# Motor_Drivers.net
KiCad netlist of a schematic drawn in Altium Designer
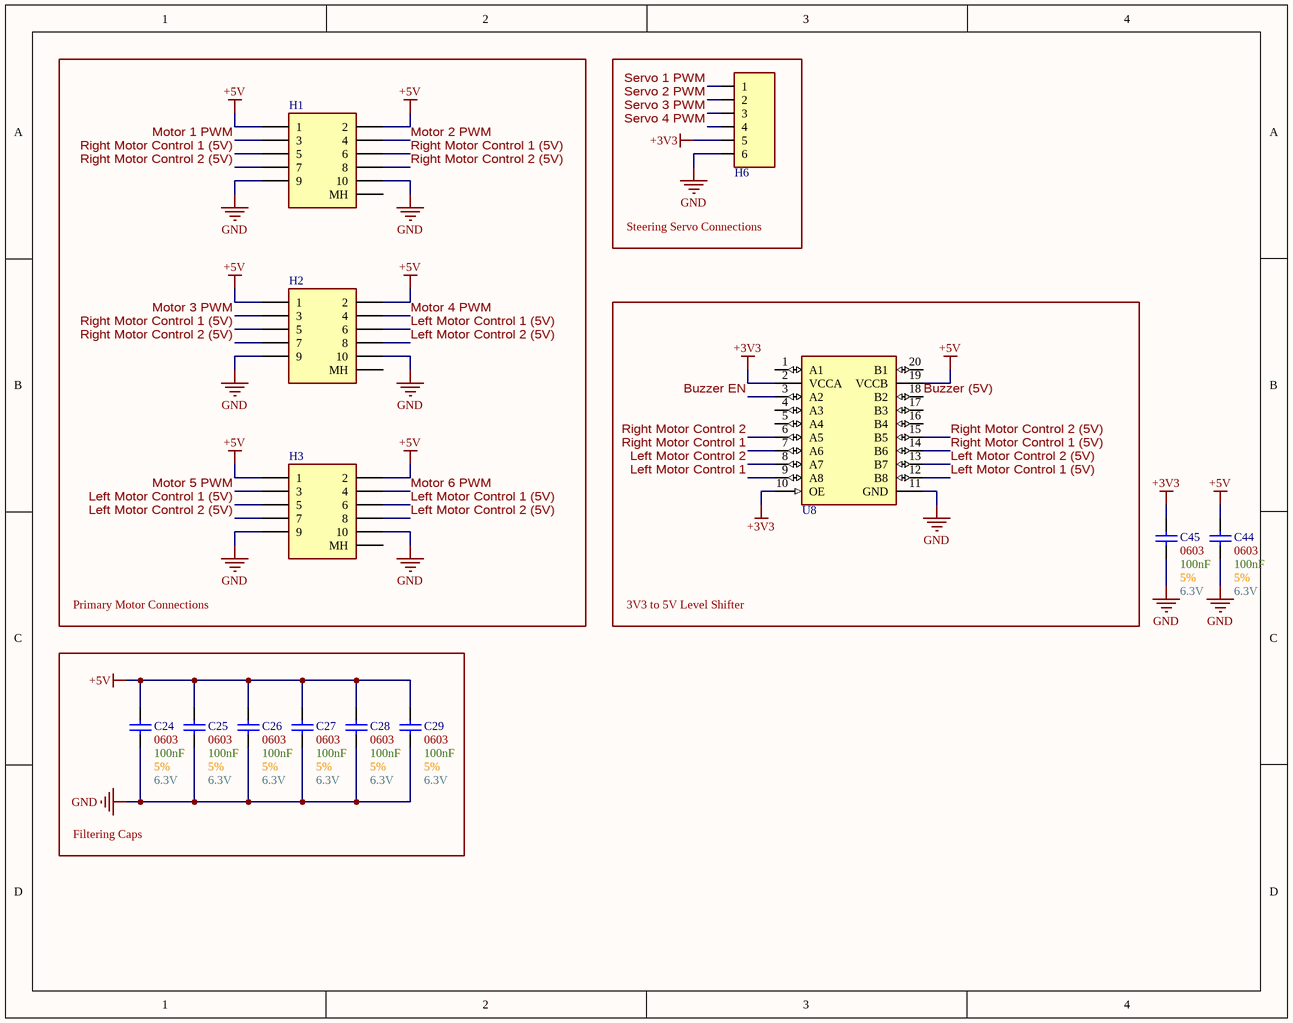
[diagram p0: Motor Drivers.SchDoc]

(export (version "E")
  (design (tool "Eeschema 10.0.6"))
  (components
    (comp (ref "C24")
      (value "[Cap] SMD Nonpolarized")
      (footprint "[Cap] SMD 0603")
      (fields
        (field (name "SIZE PACKAGE") "0603")
        (field (name "CAPACITANCE") "100nF")
        (field (name "VOLTAGE") "6.3V")
        (field (name "TOLERANCE") "5%")
      )
      (libsource (lib "RADM Components") (part "[Cap] SMD Nonpolarized"))
    )
    (comp (ref "C25")
      (value "[Cap] SMD Nonpolarized")
      (footprint "[Cap] SMD 0603")
      (fields
        (field (name "SIZE PACKAGE") "0603")
        (field (name "CAPACITANCE") "100nF")
        (field (name "VOLTAGE") "6.3V")
        (field (name "TOLERANCE") "5%")
      )
      (libsource (lib "RADM Components") (part "[Cap] SMD Nonpolarized"))
    )
    (comp (ref "C26")
      (value "[Cap] SMD Nonpolarized")
      (footprint "[Cap] SMD 0603")
      (fields
        (field (name "SIZE PACKAGE") "0603")
        (field (name "CAPACITANCE") "100nF")
        (field (name "VOLTAGE") "6.3V")
        (field (name "TOLERANCE") "5%")
      )
      (libsource (lib "RADM Components") (part "[Cap] SMD Nonpolarized"))
    )
    (comp (ref "C27")
      (value "[Cap] SMD Nonpolarized")
      (footprint "[Cap] SMD 0603")
      (fields
        (field (name "SIZE PACKAGE") "0603")
        (field (name "CAPACITANCE") "100nF")
        (field (name "VOLTAGE") "6.3V")
        (field (name "TOLERANCE") "5%")
      )
      (libsource (lib "RADM Components") (part "[Cap] SMD Nonpolarized"))
    )
    (comp (ref "C28")
      (value "[Cap] SMD Nonpolarized")
      (footprint "[Cap] SMD 0603")
      (fields
        (field (name "SIZE PACKAGE") "0603")
        (field (name "CAPACITANCE") "100nF")
        (field (name "VOLTAGE") "6.3V")
        (field (name "TOLERANCE") "5%")
      )
      (libsource (lib "RADM Components") (part "[Cap] SMD Nonpolarized"))
    )
    (comp (ref "C29")
      (value "[Cap] SMD Nonpolarized")
      (footprint "[Cap] SMD 0603")
      (fields
        (field (name "SIZE PACKAGE") "0603")
        (field (name "CAPACITANCE") "100nF")
        (field (name "VOLTAGE") "6.3V")
        (field (name "TOLERANCE") "5%")
      )
      (libsource (lib "RADM Components") (part "[Cap] SMD Nonpolarized"))
    )
    (comp (ref "C44")
      (value "[Cap] SMD Nonpolarized")
      (footprint "[Cap] SMD 0603")
      (fields
        (field (name "SIZE PACKAGE") "0603")
        (field (name "CAPACITANCE") "100nF")
        (field (name "VOLTAGE") "6.3V")
        (field (name "TOLERANCE") "5%")
      )
      (libsource (lib "RADM Components") (part "[Cap] SMD Nonpolarized"))
    )
    (comp (ref "C45")
      (value "[Cap] SMD Nonpolarized")
      (footprint "[Cap] SMD 0603")
      (fields
        (field (name "SIZE PACKAGE") "0603")
        (field (name "CAPACITANCE") "100nF")
        (field (name "VOLTAGE") "6.3V")
        (field (name "TOLERANCE") "5%")
      )
      (libsource (lib "RADM Components") (part "[Cap] SMD Nonpolarized"))
    )
    (comp (ref "H1")
      (value "[Header] Shrouded 2x5 SMD")
      (footprint "[Header] Shrouded 2x5 SMD")
      (libsource (lib "RADM Connectors") (part "[Header] Shrouded 2x5 SMD"))
    )
    (comp (ref "H2")
      (value "[Header] Shrouded 2x5 SMD")
      (footprint "[Header] Shrouded 2x5 SMD")
      (libsource (lib "RADM Connectors") (part "[Header] Shrouded 2x5 SMD"))
    )
    (comp (ref "H3")
      (value "[Header] Shrouded 2x5 SMD")
      (footprint "[Header] Shrouded 2x5 SMD")
      (libsource (lib "RADM Connectors") (part "[Header] Shrouded 2x5 SMD"))
    )
    (comp (ref "H6")
      (value "[Header] Shrouded 1x6 Male")
      (footprint "[Header] Shrouded 1x6 Male")
      (description "0705430005\r\nMates with 0050579406")
      (libsource (lib "RADM Connectors") (part "[Header] Shrouded 1x6 Male"))
    )
    (comp (ref "U8")
      (value "[IC] Level Shifter (2)")
      (footprint "[IC] Level Shifter (2)")
      (description "TXS0108EQPWRQ1")
      (libsource (lib "RADM Components") (part "[IC] Level Shifter (2)"))
    )
  )
  (nets
    (net (code "1") (name "+3V3") (class "Default")
      (node (ref "C45") (pin "2") (pinfunction "2_2") (pintype "passive"))
      (node (ref "H6") (pin "5") (pinfunction "5_5") (pintype "passive"))
      (node (ref "U8") (pin "10") (pinfunction "OE_10") (pintype "input"))
      (node (ref "U8") (pin "2") (pinfunction "VCCA_2") (pintype "power_in"))
    )
    (net (code "2") (name "+5V") (class "Default")
      (node (ref "C24") (pin "2") (pinfunction "2_2") (pintype "passive"))
      (node (ref "C25") (pin "2") (pinfunction "2_2") (pintype "passive"))
      (node (ref "C26") (pin "2") (pinfunction "2_2") (pintype "passive"))
      (node (ref "C27") (pin "2") (pinfunction "2_2") (pintype "passive"))
      (node (ref "C28") (pin "2") (pinfunction "2_2") (pintype "passive"))
      (node (ref "C29") (pin "2") (pinfunction "2_2") (pintype "passive"))
      (node (ref "C44") (pin "2") (pinfunction "2_2") (pintype "passive"))
      (node (ref "H1") (pin "1") (pinfunction "1_1") (pintype "passive"))
      (node (ref "H1") (pin "2") (pinfunction "2_2") (pintype "passive"))
      (node (ref "H2") (pin "1") (pinfunction "1_1") (pintype "passive"))
      (node (ref "H2") (pin "2") (pinfunction "2_2") (pintype "passive"))
      (node (ref "H3") (pin "1") (pinfunction "1_1") (pintype "passive"))
      (node (ref "H3") (pin "2") (pinfunction "2_2") (pintype "passive"))
      (node (ref "U8") (pin "19") (pinfunction "VCCB_19") (pintype "power_in"))
    )
    (net (code "3") (name "/Buzzer (5V)") (class "Default")
      (node (ref "U8") (pin "18") (pinfunction "B2_18") (pintype "bidirectional"))
    )
    (net (code "4") (name "/Buzzer EN") (class "Default")
      (node (ref "U8") (pin "3") (pinfunction "A2_3") (pintype "bidirectional"))
    )
    (net (code "5") (name "/Left Motor Control 1") (class "Default")
      (node (ref "U8") (pin "9") (pinfunction "A8_9") (pintype "bidirectional"))
    )
    (net (code "6") (name "/Left Motor Control 1 (5V)") (class "Default")
      (node (ref "H2") (pin "6") (pinfunction "6_6") (pintype "passive"))
      (node (ref "H3") (pin "5") (pinfunction "5_5") (pintype "passive"))
      (node (ref "H3") (pin "6") (pinfunction "6_6") (pintype "passive"))
      (node (ref "U8") (pin "12") (pinfunction "B8_12") (pintype "bidirectional"))
    )
    (net (code "7") (name "/Left Motor Control 2") (class "Default")
      (node (ref "U8") (pin "8") (pinfunction "A7_8") (pintype "bidirectional"))
    )
    (net (code "8") (name "/Left Motor Control 2 (5V)") (class "Default")
      (node (ref "H2") (pin "8") (pinfunction "8_8") (pintype "passive"))
      (node (ref "H3") (pin "7") (pinfunction "7_7") (pintype "passive"))
      (node (ref "H3") (pin "8") (pinfunction "8_8") (pintype "passive"))
      (node (ref "U8") (pin "13") (pinfunction "B7_13") (pintype "bidirectional"))
    )
    (net (code "9") (name "/Motor 1 PWM") (class "Default")
      (node (ref "H1") (pin "3") (pinfunction "3_3") (pintype "passive"))
    )
    (net (code "10") (name "/Motor 2 PWM") (class "Default")
      (node (ref "H1") (pin "4") (pinfunction "4_4") (pintype "passive"))
    )
    (net (code "11") (name "/Motor 3 PWM") (class "Default")
      (node (ref "H2") (pin "3") (pinfunction "3_3") (pintype "passive"))
    )
    (net (code "12") (name "/Motor 4 PWM") (class "Default")
      (node (ref "H2") (pin "4") (pinfunction "4_4") (pintype "passive"))
    )
    (net (code "13") (name "/Motor 5 PWM") (class "Default")
      (node (ref "H3") (pin "3") (pinfunction "3_3") (pintype "passive"))
    )
    (net (code "14") (name "/Motor 6 PWM") (class "Default")
      (node (ref "H3") (pin "4") (pinfunction "4_4") (pintype "passive"))
    )
    (net (code "15") (name "/Right Motor Control 1") (class "Default")
      (node (ref "U8") (pin "7") (pinfunction "A6_7") (pintype "bidirectional"))
    )
    (net (code "16") (name "/Right Motor Control 1 (5V)") (class "Default")
      (node (ref "H1") (pin "5") (pinfunction "5_5") (pintype "passive"))
      (node (ref "H1") (pin "6") (pinfunction "6_6") (pintype "passive"))
      (node (ref "H2") (pin "5") (pinfunction "5_5") (pintype "passive"))
      (node (ref "U8") (pin "14") (pinfunction "B6_14") (pintype "bidirectional"))
    )
    (net (code "17") (name "/Right Motor Control 2") (class "Default")
      (node (ref "U8") (pin "6") (pinfunction "A5_6") (pintype "bidirectional"))
    )
    (net (code "18") (name "/Right Motor Control 2 (5V)") (class "Default")
      (node (ref "H1") (pin "7") (pinfunction "7_7") (pintype "passive"))
      (node (ref "H1") (pin "8") (pinfunction "8_8") (pintype "passive"))
      (node (ref "H2") (pin "7") (pinfunction "7_7") (pintype "passive"))
      (node (ref "U8") (pin "15") (pinfunction "B5_15") (pintype "bidirectional"))
    )
    (net (code "19") (name "/Servo 1 PWM") (class "Default")
      (node (ref "H6") (pin "1") (pinfunction "1_1") (pintype "passive"))
    )
    (net (code "20") (name "/Servo 2 PWM") (class "Default")
      (node (ref "H6") (pin "2") (pinfunction "2_2") (pintype "passive"))
    )
    (net (code "21") (name "/Servo 3 PWM") (class "Default")
      (node (ref "H6") (pin "3") (pinfunction "3_3") (pintype "passive"))
    )
    (net (code "22") (name "/Servo 4 PWM") (class "Default")
      (node (ref "H6") (pin "4") (pinfunction "4_4") (pintype "passive"))
    )
    (net (code "23") (name "GND") (class "Default")
      (node (ref "C24") (pin "1") (pinfunction "1_1") (pintype "passive"))
      (node (ref "C25") (pin "1") (pinfunction "1_1") (pintype "passive"))
      (node (ref "C26") (pin "1") (pinfunction "1_1") (pintype "passive"))
      (node (ref "C27") (pin "1") (pinfunction "1_1") (pintype "passive"))
      (node (ref "C28") (pin "1") (pinfunction "1_1") (pintype "passive"))
      (node (ref "C29") (pin "1") (pinfunction "1_1") (pintype "passive"))
      (node (ref "C44") (pin "1") (pinfunction "1_1") (pintype "passive"))
      (node (ref "C45") (pin "1") (pinfunction "1_1") (pintype "passive"))
      (node (ref "H1") (pin "10") (pinfunction "10_10") (pintype "passive"))
      (node (ref "H1") (pin "9") (pinfunction "9_9") (pintype "passive"))
      (node (ref "H2") (pin "10") (pinfunction "10_10") (pintype "passive"))
      (node (ref "H2") (pin "9") (pinfunction "9_9") (pintype "passive"))
      (node (ref "H3") (pin "10") (pinfunction "10_10") (pintype "passive"))
      (node (ref "H3") (pin "9") (pinfunction "9_9") (pintype "passive"))
      (node (ref "H6") (pin "6") (pinfunction "6_6") (pintype "passive"))
      (node (ref "U8") (pin "11") (pinfunction "GND_11") (pintype "power_in"))
    )
    (net (code "24") (name "unconnected-(H1-MH-PadX)") (class "Default")
      (node (ref "H1") (pin "X") (pinfunction "MH_X") (pintype "passive"))
    )
    (net (code "25") (name "unconnected-(H2-MH-PadX)") (class "Default")
      (node (ref "H2") (pin "X") (pinfunction "MH_X") (pintype "passive"))
    )
    (net (code "26") (name "unconnected-(H3-MH-PadX)") (class "Default")
      (node (ref "H3") (pin "X") (pinfunction "MH_X") (pintype "passive"))
    )
    (net (code "27") (name "unconnected-(U8-A1-Pad1)") (class "Default")
      (node (ref "U8") (pin "1") (pinfunction "A1_1") (pintype "bidirectional"))
    )
    (net (code "28") (name "unconnected-(U8-A3-Pad4)") (class "Default")
      (node (ref "U8") (pin "4") (pinfunction "A3_4") (pintype "bidirectional"))
    )
    (net (code "29") (name "unconnected-(U8-A4-Pad5)") (class "Default")
      (node (ref "U8") (pin "5") (pinfunction "A4_5") (pintype "bidirectional"))
    )
    (net (code "30") (name "unconnected-(U8-B1-Pad20)") (class "Default")
      (node (ref "U8") (pin "20") (pinfunction "B1_20") (pintype "bidirectional"))
    )
    (net (code "31") (name "unconnected-(U8-B3-Pad17)") (class "Default")
      (node (ref "U8") (pin "17") (pinfunction "B3_17") (pintype "bidirectional"))
    )
    (net (code "32") (name "unconnected-(U8-B4-Pad16)") (class "Default")
      (node (ref "U8") (pin "16") (pinfunction "B4_16") (pintype "bidirectional"))
    )
  )
)
